# ETH_JTAG_SD.net
KiCad netlist of a schematic drawn in Altium Designer
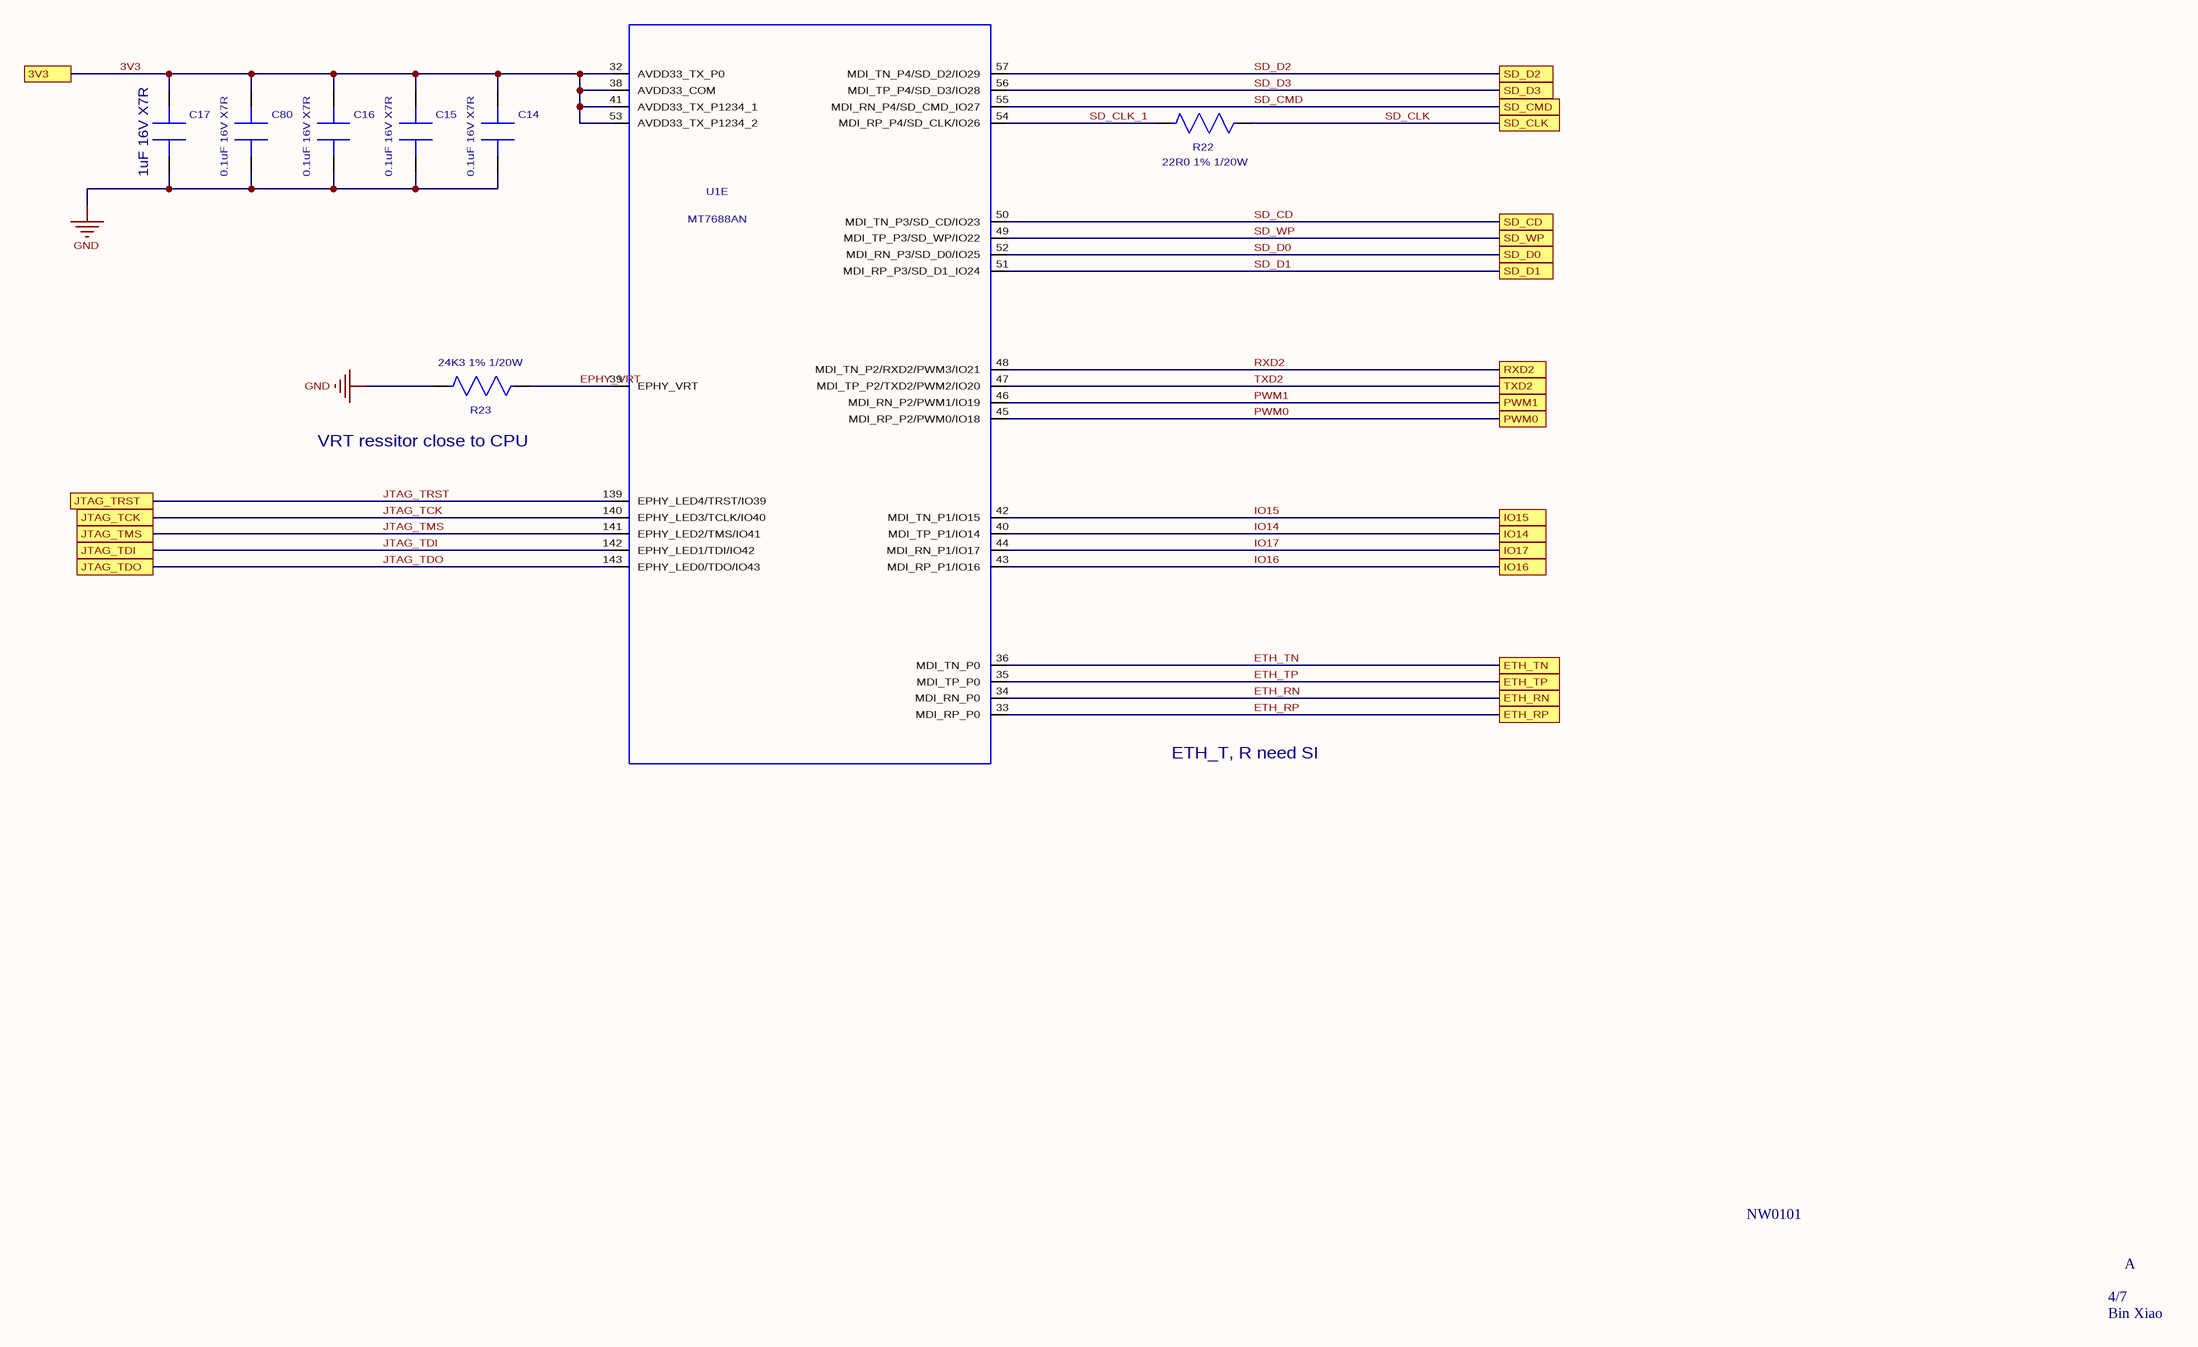
[diagram p0: ETH_JTAG_SD.SchDoc]

(export (version "E")
  (design (tool "Eeschema 10.0.6"))
  (components
    (comp (ref "C14")
      (value "0.1uF 16V X7R")
      (footprint "C0201")
      (description "CAP CER 0.1UF 16V X7R 0201")
      (fields
        (field (name "PART NUMBER") "GRM033Z71C104KE14D")
        (field (name "MANUFACTURER") "Murata Electronics")
      )
      (libsource (lib "NetworkModule") (part "CAP0201-104-16V-X7R"))
    )
    (comp (ref "C15")
      (value "0.1uF 16V X7R")
      (footprint "C0201")
      (description "CAP CER 0.1UF 16V X7R 0201")
      (fields
        (field (name "PART NUMBER") "GRM033Z71C104KE14D")
        (field (name "MANUFACTURER") "Murata Electronics")
      )
      (libsource (lib "NetworkModule") (part "CAP0201-104-16V-X7R"))
    )
    (comp (ref "C16")
      (value "0.1uF 16V X7R")
      (footprint "C0201")
      (description "CAP CER 0.1UF 16V X7R 0201")
      (fields
        (field (name "PART NUMBER") "GRM033Z71C104KE14D")
        (field (name "MANUFACTURER") "Murata Electronics")
      )
      (libsource (lib "NetworkModule") (part "CAP0201-104-16V-X7R"))
    )
    (comp (ref "C17")
      (value "1uF 16V X7R")
      (footprint "C0402")
      (description "CAP CER 1UF 6.3V X7R 0402")
      (fields
        (field (name "PART NUMBER") "GRM155R70J105KA12D")
        (field (name "MANUFACTURER") "Murata Electronics")
      )
      (libsource (lib "NetworkModule") (part "CAP0402-105-6.3V-X7R"))
    )
    (comp (ref "C80")
      (value "0.1uF 16V X7R")
      (footprint "C0201")
      (description "CAP CER 0.1UF 16V X7R 0201")
      (fields
        (field (name "PART NUMBER") "GRM033Z71C104KE14D")
        (field (name "MANUFACTURER") "Murata Electronics")
      )
      (libsource (lib "NetworkModule") (part "CAP0201-104-16V-X7R"))
    )
    (comp (ref "R22")
      (value "22R0 1% 1/20W")
      (footprint "R0201")
      (description "RES 22 OHM 1% 1/20W 0201")
      (fields (field (name "MANUFACTURER") "Yageo") (field (name "PART NUMBER") "RC0201FR-0722RL"))
      (libsource (lib "NetworkModule") (part "RES0201-22R0"))
    )
    (comp (ref "R23")
      (value "24K3 1% 1/20W")
      (footprint "R0201")
      (description "RES 24.3K OHM 1% 1/20W 0201")
      (fields (field (name "PART NUMBER") "RC0201FR-0724K3L") (field (name "MANUFACTURER") "YAGEO"))
      (libsource (lib "NetworkModule") (part "RES0201-24K3"))
    )
    (comp (ref "U1")
      (value "MT7688AN")
      (footprint "DR-QFN-128")
      (description "580Mhz 32bits Networking Processor")
      (fields (field (name "MANUFACTURER") "MediaTek Inc"))
      (libsource (lib "*") (part "MT7688AN"))
    )
  )
  (nets
    (net (code "1") (name "/3V3") (class "Default")
      (node (ref "C14") (pin "1") (pinfunction "1_1") (pintype "passive"))
      (node (ref "C15") (pin "1") (pinfunction "1_1") (pintype "passive"))
      (node (ref "C16") (pin "1") (pinfunction "1_1") (pintype "passive"))
      (node (ref "C17") (pin "1") (pinfunction "1_1") (pintype "passive"))
      (node (ref "C80") (pin "1") (pinfunction "1_1") (pintype "passive"))
      (node (ref "U1") (pin "32") (pinfunction "AVDD33_TX_P0_32") (pintype "passive"))
      (node (ref "U1") (pin "38") (pinfunction "AVDD33_COM_38") (pintype "passive"))
      (node (ref "U1") (pin "41") (pinfunction "AVDD33_TX_P1234_1_41") (pintype "passive"))
      (node (ref "U1") (pin "53") (pinfunction "AVDD33_TX_P1234_2_53") (pintype "passive"))
    )
    (net (code "2") (name "/EPHY_VRT") (class "Default")
      (node (ref "R23") (pin "1") (pinfunction "1_1") (pintype "passive"))
      (node (ref "U1") (pin "39") (pinfunction "EPHY_VRT_39") (pintype "passive"))
    )
    (net (code "3") (name "/ETH_RN") (class "Default")
      (node (ref "U1") (pin "34") (pinfunction "MDI_RN_P0_34") (pintype "passive"))
    )
    (net (code "4") (name "/ETH_RP") (class "Default")
      (node (ref "U1") (pin "33") (pinfunction "MDI_RP_P0_33") (pintype "passive"))
    )
    (net (code "5") (name "/ETH_TN") (class "Default")
      (node (ref "U1") (pin "36") (pinfunction "MDI_TN_P0_36") (pintype "passive"))
    )
    (net (code "6") (name "/ETH_TP") (class "Default")
      (node (ref "U1") (pin "35") (pinfunction "MDI_TP_P0_35") (pintype "passive"))
    )
    (net (code "7") (name "/IO14") (class "Default")
      (node (ref "U1") (pin "40") (pinfunction "MDI_TP_P1/IO14_40") (pintype "passive"))
    )
    (net (code "8") (name "/IO15") (class "Default")
      (node (ref "U1") (pin "42") (pinfunction "MDI_TN_P1/IO15_42") (pintype "passive"))
    )
    (net (code "9") (name "/IO16") (class "Default")
      (node (ref "U1") (pin "43") (pinfunction "MDI_RP_P1/IO16_43") (pintype "passive"))
    )
    (net (code "10") (name "/IO17") (class "Default")
      (node (ref "U1") (pin "44") (pinfunction "MDI_RN_P1/IO17_44") (pintype "passive"))
    )
    (net (code "11") (name "/JTAG_TCK") (class "Default")
      (node (ref "U1") (pin "140") (pinfunction "EPHY_LED3/TCLK/IO40_140") (pintype "passive"))
    )
    (net (code "12") (name "/JTAG_TDI") (class "Default")
      (node (ref "U1") (pin "142") (pinfunction "EPHY_LED1/TDI/IO42_142") (pintype "passive"))
    )
    (net (code "13") (name "/JTAG_TDO") (class "Default")
      (node (ref "U1") (pin "143") (pinfunction "EPHY_LED0/TDO/IO43_143") (pintype "passive"))
    )
    (net (code "14") (name "/JTAG_TMS") (class "Default")
      (node (ref "U1") (pin "141") (pinfunction "EPHY_LED2/TMS/IO41_141") (pintype "passive"))
    )
    (net (code "15") (name "/JTAG_TRST") (class "Default")
      (node (ref "U1") (pin "139") (pinfunction "EPHY_LED4/TRST/IO39_139") (pintype "passive"))
    )
    (net (code "16") (name "/PWM0") (class "Default")
      (node (ref "U1") (pin "45") (pinfunction "MDI_RP_P2/PWM0/IO18_45") (pintype "passive"))
    )
    (net (code "17") (name "/PWM1") (class "Default")
      (node (ref "U1") (pin "46") (pinfunction "MDI_RN_P2/PWM1/IO19_46") (pintype "passive"))
    )
    (net (code "18") (name "/RXD2") (class "Default")
      (node (ref "U1") (pin "48") (pinfunction "MDI_TN_P2/RXD2/PWM3/IO21_48") (pintype "passive"))
    )
    (net (code "19") (name "/SD_CD") (class "Default")
      (node (ref "U1") (pin "50") (pinfunction "MDI_TN_P3/SD_CD/IO23_50") (pintype "passive"))
    )
    (net (code "20") (name "/SD_CLK") (class "Default")
      (node (ref "R22") (pin "1") (pinfunction "1_1") (pintype "passive"))
    )
    (net (code "21") (name "/SD_CLK_1") (class "Default")
      (node (ref "R22") (pin "2") (pinfunction "2_2") (pintype "passive"))
      (node (ref "U1") (pin "54") (pinfunction "MDI_RP_P4/SD_CLK/IO26_54") (pintype "passive"))
    )
    (net (code "22") (name "/SD_CMD") (class "Default")
      (node (ref "U1") (pin "55") (pinfunction "MDI_RN_P4/SD_CMD_IO27_55") (pintype "passive"))
    )
    (net (code "23") (name "/SD_D0") (class "Default")
      (node (ref "U1") (pin "52") (pinfunction "MDI_RN_P3/SD_D0/IO25_52") (pintype "passive"))
    )
    (net (code "24") (name "/SD_D1") (class "Default")
      (node (ref "U1") (pin "51") (pinfunction "MDI_RP_P3/SD_D1_IO24_51") (pintype "passive"))
    )
    (net (code "25") (name "/SD_D2") (class "Default")
      (node (ref "U1") (pin "57") (pinfunction "MDI_TN_P4/SD_D2/IO29_57") (pintype "passive"))
    )
    (net (code "26") (name "/SD_D3") (class "Default")
      (node (ref "U1") (pin "56") (pinfunction "MDI_TP_P4/SD_D3/IO28_56") (pintype "passive"))
    )
    (net (code "27") (name "/SD_WP") (class "Default")
      (node (ref "U1") (pin "49") (pinfunction "MDI_TP_P3/SD_WP/IO22_49") (pintype "passive"))
    )
    (net (code "28") (name "/TXD2") (class "Default")
      (node (ref "U1") (pin "47") (pinfunction "MDI_TP_P2/TXD2/PWM2/IO20_47") (pintype "passive"))
    )
    (net (code "29") (name "GND") (class "Default")
      (node (ref "C14") (pin "2") (pinfunction "2_2") (pintype "passive"))
      (node (ref "C15") (pin "2") (pinfunction "2_2") (pintype "passive"))
      (node (ref "C16") (pin "2") (pinfunction "2_2") (pintype "passive"))
      (node (ref "C17") (pin "2") (pinfunction "2_2") (pintype "passive"))
      (node (ref "C80") (pin "2") (pinfunction "2_2") (pintype "passive"))
      (node (ref "R23") (pin "2") (pinfunction "2_2") (pintype "passive"))
    )
  )
)
